# ROB_v2.net
KiCad netlist of a schematic drawn in EAGLE
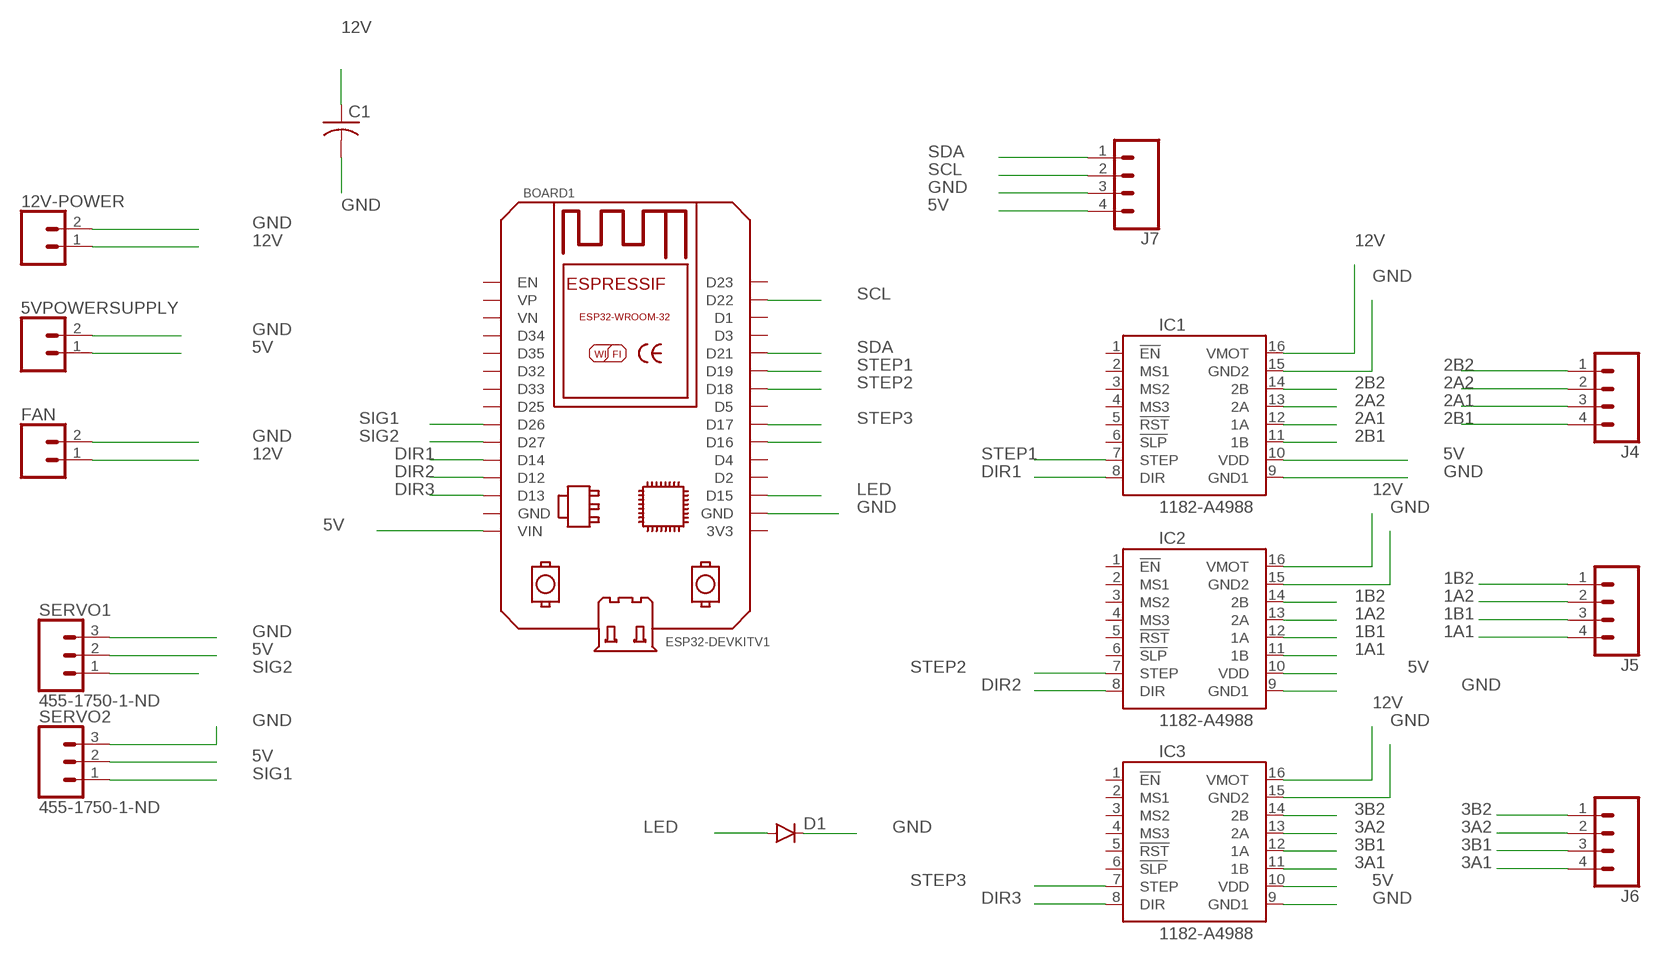
[diagram p0: schematic, sheet 1]

(export (version "E")
  (design (tool "Eeschema 10.0.6"))
  (components
    (comp (ref "5VPOWERSUPPLY")
      (value "CONN_02")
      (footprint "eagle-import:1X02")
      (libsource (lib "eagle-import") (part "CONN_02"))
    )
    (comp (ref "12V-POWER")
      (value "CONN_02")
      (footprint "eagle-import:1X02")
      (libsource (lib "eagle-import") (part "CONN_02"))
    )
    (comp (ref "BOARD1")
      (value "ESP32DEVKITV1")
      (footprint "eagle-import:ESP32-DEVKITV1")
      (libsource (lib "eagle-import") (part "ESP32DEVKITV1"))
    )
    (comp (ref "C1")
      (value "C-US050-075X075")
      (footprint "eagle-import:C050-075X075")
      (libsource (lib "eagle-import") (part "C-US050-075X075"))
    )
    (comp (ref "D1")
      (value "DIODE")
      (footprint "eagle-import:DIODE-1N4001-KIT")
      (libsource (lib "eagle-import") (part "DIODE"))
    )
    (comp (ref "FAN")
      (value "CONN_02")
      (footprint "eagle-import:1X02")
      (libsource (lib "eagle-import") (part "CONN_02"))
    )
    (comp (ref "IC1")
      (value "1182-A4988")
      (footprint "eagle-import:A4988")
      (libsource (lib "eagle-import") (part "1182-A4988"))
    )
    (comp (ref "IC2")
      (value "1182-A4988")
      (footprint "eagle-import:A4988")
      (libsource (lib "eagle-import") (part "1182-A4988"))
    )
    (comp (ref "IC3")
      (value "1182-A4988")
      (footprint "eagle-import:A4988")
      (libsource (lib "eagle-import") (part "1182-A4988"))
    )
    (comp (ref "J4")
      (value "CONN_04LONGPADS")
      (footprint "eagle-import:1X04_LONGPADS")
      (libsource (lib "eagle-import") (part "CONN_04LONGPADS"))
    )
    (comp (ref "J5")
      (value "CONN_04LONGPADS")
      (footprint "eagle-import:1X04_LONGPADS")
      (libsource (lib "eagle-import") (part "CONN_04LONGPADS"))
    )
    (comp (ref "J6")
      (value "CONN_04LONGPADS")
      (footprint "eagle-import:1X04_LONGPADS")
      (libsource (lib "eagle-import") (part "CONN_04LONGPADS"))
    )
    (comp (ref "J7")
      (value "CONN_04LOCK")
      (footprint "eagle-import:1X04_LOCK")
      (libsource (lib "eagle-import") (part "CONN_04LOCK"))
    )
    (comp (ref "SERVO1")
      (value "455-1750-1-ND")
      (footprint "eagle-import:1X03")
      (libsource (lib "eagle-import") (part "CONN_03"))
    )
    (comp (ref "SERVO2")
      (value "455-1750-1-ND")
      (footprint "eagle-import:1X03")
      (libsource (lib "eagle-import") (part "CONN_03"))
    )
  )
  (nets
    (net (code "1") (name "/1A1") (class "Default")
      (node (ref "IC2") (pin "11") (pinfunction "1B_11") (pintype "output"))
      (node (ref "J5") (pin "4") (pinfunction "4_4") (pintype "passive"))
    )
    (net (code "2") (name "/1A2") (class "Default")
      (node (ref "IC2") (pin "13") (pinfunction "2A_13") (pintype "output"))
      (node (ref "J5") (pin "2") (pinfunction "2_2") (pintype "passive"))
    )
    (net (code "3") (name "/1B1") (class "Default")
      (node (ref "IC2") (pin "12") (pinfunction "1A_12") (pintype "output"))
      (node (ref "J5") (pin "3") (pinfunction "3_3") (pintype "passive"))
    )
    (net (code "4") (name "/1B2") (class "Default")
      (node (ref "IC2") (pin "14") (pinfunction "2B_14") (pintype "output"))
      (node (ref "J5") (pin "1") (pinfunction "1_1") (pintype "passive"))
    )
    (net (code "5") (name "/2A1") (class "Default")
      (node (ref "IC1") (pin "12") (pinfunction "1A_12") (pintype "output"))
      (node (ref "J4") (pin "3") (pinfunction "3_3") (pintype "passive"))
    )
    (net (code "6") (name "/2A2") (class "Default")
      (node (ref "IC1") (pin "13") (pinfunction "2A_13") (pintype "output"))
      (node (ref "J4") (pin "2") (pinfunction "2_2") (pintype "passive"))
    )
    (net (code "7") (name "/2B1") (class "Default")
      (node (ref "IC1") (pin "11") (pinfunction "1B_11") (pintype "output"))
      (node (ref "J4") (pin "4") (pinfunction "4_4") (pintype "passive"))
    )
    (net (code "8") (name "/2B2") (class "Default")
      (node (ref "IC1") (pin "14") (pinfunction "2B_14") (pintype "output"))
      (node (ref "J4") (pin "1") (pinfunction "1_1") (pintype "passive"))
    )
    (net (code "9") (name "/3A1") (class "Default")
      (node (ref "IC3") (pin "11") (pinfunction "1B_11") (pintype "output"))
      (node (ref "J6") (pin "4") (pinfunction "4_4") (pintype "passive"))
    )
    (net (code "10") (name "/3A2") (class "Default")
      (node (ref "IC3") (pin "13") (pinfunction "2A_13") (pintype "output"))
      (node (ref "J6") (pin "2") (pinfunction "2_2") (pintype "passive"))
    )
    (net (code "11") (name "/3B1") (class "Default")
      (node (ref "IC3") (pin "12") (pinfunction "1A_12") (pintype "output"))
      (node (ref "J6") (pin "3") (pinfunction "3_3") (pintype "passive"))
    )
    (net (code "12") (name "/3B2") (class "Default")
      (node (ref "IC3") (pin "14") (pinfunction "2B_14") (pintype "output"))
      (node (ref "J6") (pin "1") (pinfunction "1_1") (pintype "passive"))
    )
    (net (code "13") (name "/5V") (class "Default")
      (node (ref "5VPOWERSUPPLY") (pin "1") (pinfunction "1_1") (pintype "passive"))
      (node (ref "BOARD1") (pin "VIN") (pinfunction "VIN_VIN") (pintype "bidirectional"))
      (node (ref "IC1") (pin "10") (pinfunction "VDD_10") (pintype "power_in"))
      (node (ref "IC2") (pin "10") (pinfunction "VDD_10") (pintype "power_in"))
      (node (ref "IC3") (pin "10") (pinfunction "VDD_10") (pintype "power_in"))
      (node (ref "J7") (pin "4") (pinfunction "4_4") (pintype "passive"))
      (node (ref "SERVO1") (pin "2") (pinfunction "2_2") (pintype "passive"))
      (node (ref "SERVO2") (pin "2") (pinfunction "2_2") (pintype "passive"))
    )
    (net (code "14") (name "/12V") (class "Default")
      (node (ref "12V-POWER") (pin "1") (pinfunction "1_1") (pintype "passive"))
      (node (ref "C1") (pin "1") (pinfunction "1_1") (pintype "passive"))
      (node (ref "FAN") (pin "1") (pinfunction "1_1") (pintype "passive"))
      (node (ref "IC1") (pin "16") (pinfunction "VMOT_16") (pintype "power_in"))
      (node (ref "IC2") (pin "16") (pinfunction "VMOT_16") (pintype "power_in"))
      (node (ref "IC3") (pin "16") (pinfunction "VMOT_16") (pintype "power_in"))
    )
    (net (code "15") (name "/DIR1") (class "Default")
      (node (ref "BOARD1") (pin "D14") (pinfunction "D14_D14") (pintype "bidirectional"))
      (node (ref "IC1") (pin "8") (pinfunction "DIR_8") (pintype "input"))
    )
    (net (code "16") (name "/DIR2") (class "Default")
      (node (ref "BOARD1") (pin "D12") (pinfunction "D12_D12") (pintype "bidirectional"))
      (node (ref "IC2") (pin "8") (pinfunction "DIR_8") (pintype "input"))
    )
    (net (code "17") (name "/DIR3") (class "Default")
      (node (ref "BOARD1") (pin "D13") (pinfunction "D13_D13") (pintype "bidirectional"))
      (node (ref "IC3") (pin "8") (pinfunction "DIR_8") (pintype "input"))
    )
    (net (code "18") (name "/GND") (class "Default")
      (node (ref "12V-POWER") (pin "2") (pinfunction "2_2") (pintype "passive"))
      (node (ref "5VPOWERSUPPLY") (pin "2") (pinfunction "2_2") (pintype "passive"))
      (node (ref "BOARD1") (pin "GND@1") (pinfunction "GND_GND@1") (pintype "bidirectional"))
      (node (ref "C1") (pin "2") (pinfunction "2_2") (pintype "passive"))
      (node (ref "D1") (pin "C") (pinfunction "C_C") (pintype "passive"))
      (node (ref "FAN") (pin "2") (pinfunction "2_2") (pintype "passive"))
      (node (ref "IC1") (pin "15") (pinfunction "GND2_15") (pintype "power_in"))
      (node (ref "IC1") (pin "9") (pinfunction "GND1_9") (pintype "power_in"))
      (node (ref "IC2") (pin "15") (pinfunction "GND2_15") (pintype "power_in"))
      (node (ref "IC2") (pin "9") (pinfunction "GND1_9") (pintype "power_in"))
      (node (ref "IC3") (pin "15") (pinfunction "GND2_15") (pintype "power_in"))
      (node (ref "IC3") (pin "9") (pinfunction "GND1_9") (pintype "power_in"))
      (node (ref "J7") (pin "3") (pinfunction "3_3") (pintype "passive"))
      (node (ref "SERVO1") (pin "3") (pinfunction "3_3") (pintype "passive"))
      (node (ref "SERVO2") (pin "3") (pinfunction "3_3") (pintype "passive"))
    )
    (net (code "19") (name "/LED") (class "Default")
      (node (ref "BOARD1") (pin "D15") (pinfunction "D15_D15") (pintype "bidirectional"))
      (node (ref "D1") (pin "A") (pinfunction "A_A") (pintype "passive"))
    )
    (net (code "20") (name "/SCL") (class "Default")
      (node (ref "BOARD1") (pin "D22") (pinfunction "D22_D22") (pintype "bidirectional"))
      (node (ref "J7") (pin "2") (pinfunction "2_2") (pintype "passive"))
    )
    (net (code "21") (name "/SDA") (class "Default")
      (node (ref "BOARD1") (pin "D21") (pinfunction "D21_D21") (pintype "bidirectional"))
      (node (ref "J7") (pin "1") (pinfunction "1_1") (pintype "passive"))
    )
    (net (code "22") (name "/SIG1") (class "Default")
      (node (ref "BOARD1") (pin "D26") (pinfunction "D26_D26") (pintype "bidirectional"))
      (node (ref "SERVO2") (pin "1") (pinfunction "1_1") (pintype "passive"))
    )
    (net (code "23") (name "/SIG2") (class "Default")
      (node (ref "BOARD1") (pin "D27") (pinfunction "D27_D27") (pintype "bidirectional"))
      (node (ref "SERVO1") (pin "1") (pinfunction "1_1") (pintype "passive"))
    )
    (net (code "24") (name "/STEP1") (class "Default")
      (node (ref "BOARD1") (pin "D19") (pinfunction "D19_D19") (pintype "bidirectional"))
      (node (ref "IC1") (pin "7") (pinfunction "STEP_7") (pintype "input"))
    )
    (net (code "25") (name "/STEP2") (class "Default")
      (node (ref "BOARD1") (pin "D18") (pinfunction "D18_D18") (pintype "bidirectional"))
      (node (ref "IC2") (pin "7") (pinfunction "STEP_7") (pintype "input"))
    )
    (net (code "26") (name "/STEP3") (class "Default")
      (node (ref "BOARD1") (pin "D17") (pinfunction "D17_D17") (pintype "bidirectional"))
      (node (ref "IC3") (pin "7") (pinfunction "STEP_7") (pintype "input"))
    )
    (net (code "27") (name "unconnected-(BOARD1-Pad3V3)") (class "Default")
      (node (ref "BOARD1") (pin "3V3") (pinfunction "3V3_3V3") (pintype "bidirectional"))
    )
    (net (code "28") (name "unconnected-(BOARD1-PadD1)") (class "Default")
      (node (ref "BOARD1") (pin "D1") (pinfunction "D1_D1") (pintype "bidirectional"))
    )
    (net (code "29") (name "unconnected-(BOARD1-PadD2)") (class "Default")
      (node (ref "BOARD1") (pin "D2") (pinfunction "D2_D2") (pintype "bidirectional"))
    )
    (net (code "30") (name "unconnected-(BOARD1-PadD3)") (class "Default")
      (node (ref "BOARD1") (pin "D3") (pinfunction "D3_D3") (pintype "bidirectional"))
    )
    (net (code "31") (name "unconnected-(BOARD1-PadD4)") (class "Default")
      (node (ref "BOARD1") (pin "D4") (pinfunction "D4_D4") (pintype "bidirectional"))
    )
    (net (code "32") (name "unconnected-(BOARD1-PadD5)") (class "Default")
      (node (ref "BOARD1") (pin "D5") (pinfunction "D5_D5") (pintype "bidirectional"))
    )
    (net (code "33") (name "unconnected-(BOARD1-PadD16)") (class "Default")
      (node (ref "BOARD1") (pin "D16") (pinfunction "D16_D16") (pintype "bidirectional"))
    )
    (net (code "34") (name "unconnected-(BOARD1-PadD23)") (class "Default")
      (node (ref "BOARD1") (pin "D23") (pinfunction "D23_D23") (pintype "bidirectional"))
    )
    (net (code "35") (name "unconnected-(BOARD1-PadD25)") (class "Default")
      (node (ref "BOARD1") (pin "D25") (pinfunction "D25_D25") (pintype "bidirectional"))
    )
    (net (code "36") (name "unconnected-(BOARD1-PadD32)") (class "Default")
      (node (ref "BOARD1") (pin "D32") (pinfunction "D32_D32") (pintype "bidirectional"))
    )
    (net (code "37") (name "unconnected-(BOARD1-PadD33)") (class "Default")
      (node (ref "BOARD1") (pin "D33") (pinfunction "D33_D33") (pintype "bidirectional"))
    )
    (net (code "38") (name "unconnected-(BOARD1-PadD34)") (class "Default")
      (node (ref "BOARD1") (pin "D34") (pinfunction "D34_D34") (pintype "bidirectional"))
    )
    (net (code "39") (name "unconnected-(BOARD1-PadD35)") (class "Default")
      (node (ref "BOARD1") (pin "D35") (pinfunction "D35_D35") (pintype "bidirectional"))
    )
    (net (code "40") (name "unconnected-(BOARD1-PadEN)") (class "Default")
      (node (ref "BOARD1") (pin "EN") (pinfunction "EN_EN") (pintype "bidirectional"))
    )
    (net (code "41") (name "unconnected-(BOARD1-PadGND)") (class "Default")
      (node (ref "BOARD1") (pin "GND") (pinfunction "GND_GND") (pintype "bidirectional"))
    )
    (net (code "42") (name "unconnected-(BOARD1-PadVN)") (class "Default")
      (node (ref "BOARD1") (pin "VN") (pinfunction "VN_VN") (pintype "bidirectional"))
    )
    (net (code "43") (name "unconnected-(BOARD1-PadVP)") (class "Default")
      (node (ref "BOARD1") (pin "VP") (pinfunction "VP_VP") (pintype "bidirectional"))
    )
    (net (code "44") (name "unconnected-(IC1-MS1-Pad2)") (class "Default")
      (node (ref "IC1") (pin "2") (pinfunction "MS1_2") (pintype "passive"))
    )
    (net (code "45") (name "unconnected-(IC1-MS2-Pad3)") (class "Default")
      (node (ref "IC1") (pin "3") (pinfunction "MS2_3") (pintype "passive"))
    )
    (net (code "46") (name "unconnected-(IC1-MS3-Pad4)") (class "Default")
      (node (ref "IC1") (pin "4") (pinfunction "MS3_4") (pintype "passive"))
    )
    (net (code "47") (name "unconnected-(IC1-~{EN}-Pad1)") (class "Default")
      (node (ref "IC1") (pin "1") (pinfunction "~{EN}_1") (pintype "passive"))
    )
    (net (code "48") (name "unconnected-(IC1-~{RST}-Pad5)") (class "Default")
      (node (ref "IC1") (pin "5") (pinfunction "~{RST}_5") (pintype "passive"))
    )
    (net (code "49") (name "unconnected-(IC1-~{SLP}-Pad6)") (class "Default")
      (node (ref "IC1") (pin "6") (pinfunction "~{SLP}_6") (pintype "passive"))
    )
    (net (code "50") (name "unconnected-(IC2-MS1-Pad2)") (class "Default")
      (node (ref "IC2") (pin "2") (pinfunction "MS1_2") (pintype "passive"))
    )
    (net (code "51") (name "unconnected-(IC2-MS2-Pad3)") (class "Default")
      (node (ref "IC2") (pin "3") (pinfunction "MS2_3") (pintype "passive"))
    )
    (net (code "52") (name "unconnected-(IC2-MS3-Pad4)") (class "Default")
      (node (ref "IC2") (pin "4") (pinfunction "MS3_4") (pintype "passive"))
    )
    (net (code "53") (name "unconnected-(IC2-~{EN}-Pad1)") (class "Default")
      (node (ref "IC2") (pin "1") (pinfunction "~{EN}_1") (pintype "passive"))
    )
    (net (code "54") (name "unconnected-(IC2-~{RST}-Pad5)") (class "Default")
      (node (ref "IC2") (pin "5") (pinfunction "~{RST}_5") (pintype "passive"))
    )
    (net (code "55") (name "unconnected-(IC2-~{SLP}-Pad6)") (class "Default")
      (node (ref "IC2") (pin "6") (pinfunction "~{SLP}_6") (pintype "passive"))
    )
    (net (code "56") (name "unconnected-(IC3-MS1-Pad2)") (class "Default")
      (node (ref "IC3") (pin "2") (pinfunction "MS1_2") (pintype "passive"))
    )
    (net (code "57") (name "unconnected-(IC3-MS2-Pad3)") (class "Default")
      (node (ref "IC3") (pin "3") (pinfunction "MS2_3") (pintype "passive"))
    )
    (net (code "58") (name "unconnected-(IC3-MS3-Pad4)") (class "Default")
      (node (ref "IC3") (pin "4") (pinfunction "MS3_4") (pintype "passive"))
    )
    (net (code "59") (name "unconnected-(IC3-~{EN}-Pad1)") (class "Default")
      (node (ref "IC3") (pin "1") (pinfunction "~{EN}_1") (pintype "passive"))
    )
    (net (code "60") (name "unconnected-(IC3-~{RST}-Pad5)") (class "Default")
      (node (ref "IC3") (pin "5") (pinfunction "~{RST}_5") (pintype "passive"))
    )
    (net (code "61") (name "unconnected-(IC3-~{SLP}-Pad6)") (class "Default")
      (node (ref "IC3") (pin "6") (pinfunction "~{SLP}_6") (pintype "passive"))
    )
  )
)
